# Peripherals.net
KiCad netlist of a schematic drawn in Altium Designer
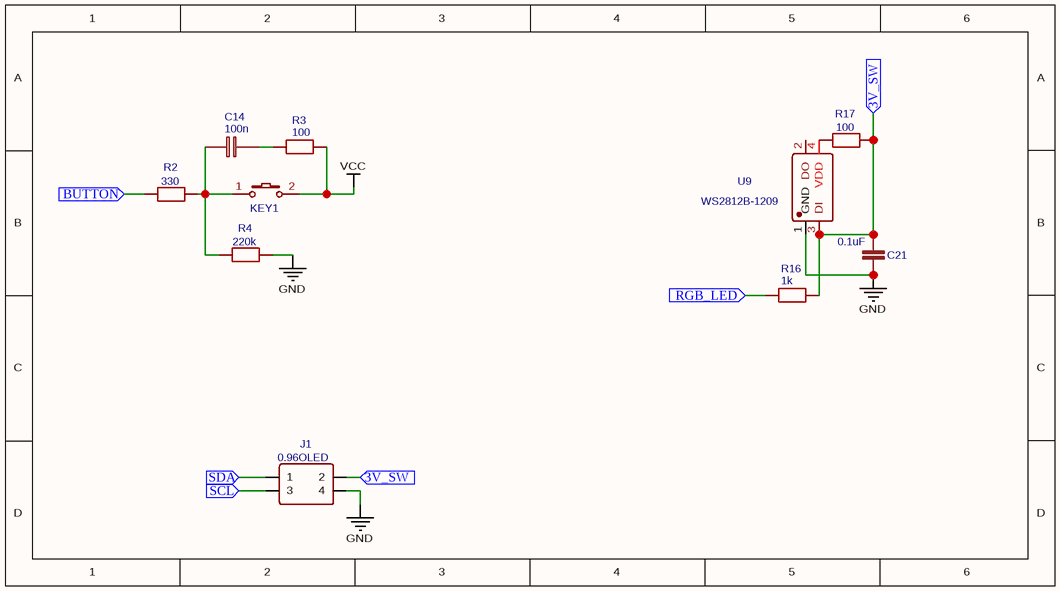
[diagram p0: Peripherals.schdoc]

(export (version "E")
  (design (tool "Eeschema 10.0.6"))
  (components
    (comp (ref "C14")
      (value "100n")
      (fields (field (name "CONTRIBUTOR") "LCEDA_Lib"))
      (libsource (lib "altium-import") (part "root_0_100n_"))
    )
    (comp (ref "C21")
      (value "0.1uF")
      (description "CAP-00810")
      (fields (field (name "CONTRIBUTOR") "SparkFun"))
      (libsource (lib "altium-import") (part "root_0_0.1uF_"))
    )
    (comp (ref "J1")
      (value "0.96OLED")
      (fields (field (name "BOM_SUPPLIER PART") "C66690") (field (name "CONTRIBUTOR") "LCEDA_Lib"))
      (libsource (lib "altium-import") (part "root_0_0.96OLED_"))
    )
    (comp (ref "KEY1")
      (value "K2-3.6×6.1_SMD")
      (fields
        (field (name "BOM_SUPPLIER PART") "C118141")
        (field (name "BOM_MANUFACTURER PART") "K2-1107ST-A4SW-06")
        (field (name "CONTRIBUTOR") "LCEDA_Lib")
      )
      (libsource (lib "altium-import") (part "root_0_K2-3.6×6.1_SMD_"))
    )
    (comp (ref "R2")
      (value "330")
      (fields (field (name "CONTRIBUTOR") "LCEDA_Lib"))
      (libsource (lib "altium-import") (part "root_0_330_"))
    )
    (comp (ref "R3")
      (value "100")
      (fields (field (name "CONTRIBUTOR") "LCEDA_Lib"))
      (libsource (lib "altium-import") (part "root_0_100_"))
    )
    (comp (ref "R4")
      (value "220k")
      (fields (field (name "CONTRIBUTOR") "LCEDA_Lib"))
      (libsource (lib "altium-import") (part "root_0_220k_"))
    )
    (comp (ref "R16")
      (value "1k")
      (fields
        (field (name "BOM_SUPPLIER PART") "C525388")
        (field (name "BOM_MANUFACTURER PART") "TCTR0603F47K0F3960T")
        (field (name "CONTRIBUTOR") "LCSC")
      )
      (libsource (lib "altium-import") (part "root_2_1k_"))
    )
    (comp (ref "R17")
      (value "100")
      (fields
        (field (name "BOM_SUPPLIER PART") "C525388")
        (field (name "BOM_MANUFACTURER PART") "TCTR0603F47K0F3960T")
        (field (name "CONTRIBUTOR") "LCSC")
      )
      (libsource (lib "altium-import") (part "root_0_100_"))
    )
    (comp (ref "U9")
      (value "WS2812B-1209")
      (fields (field (name "BOM_SUPPLIER PART") "C2835111") (field (name "CONTRIBUTOR") "LCSC"))
      (libsource (lib "altium-import") (part "root_1_WS2812B-1209_"))
    )
  )
  (nets
    (net (code "1") (name "/3V_SW") (class "Default")
      (node (ref "C21") (pin "1") (pinfunction "1_1") (pintype "passive"))
      (node (ref "J1") (pin "2") (pinfunction "2_2") (pintype "passive"))
      (node (ref "R16") (pin "1") (pinfunction "1_1") (pintype "passive"))
      (node (ref "R17") (pin "2") (pinfunction "2_2") (pintype "passive"))
      (node (ref "U9") (pin "3") (pinfunction "DI_3") (pintype "passive"))
    )
    (net (code "2") (name "/BUTTON") (class "Default")
      (node (ref "R2") (pin "1") (pinfunction "1_1") (pintype "passive"))
    )
    (net (code "3") (name "/RGB_LED") (class "Default")
      (node (ref "R16") (pin "2") (pinfunction "2_2") (pintype "passive"))
    )
    (net (code "4") (name "/SCL") (class "Default")
      (node (ref "J1") (pin "3") (pinfunction "3_3") (pintype "passive"))
    )
    (net (code "5") (name "/SDA") (class "Default")
      (node (ref "J1") (pin "1") (pinfunction "1_1") (pintype "passive"))
    )
    (net (code "6") (name "GND") (class "Default")
      (node (ref "C21") (pin "2") (pinfunction "2_2") (pintype "passive"))
      (node (ref "J1") (pin "4") (pinfunction "4_4") (pintype "passive"))
      (node (ref "R4") (pin "2") (pinfunction "2_2") (pintype "passive"))
      (node (ref "U9") (pin "1") (pinfunction "GND_1") (pintype "passive"))
    )
    (net (code "7") (name "Net-(C14-Pad1)") (class "Default")
      (node (ref "C14") (pin "1") (pinfunction "1_1") (pintype "passive"))
      (node (ref "KEY1") (pin "1") (pinfunction "1_1") (pintype "passive"))
      (node (ref "R2") (pin "2") (pinfunction "2_2") (pintype "passive"))
      (node (ref "R4") (pin "1") (pinfunction "1_1") (pintype "passive"))
    )
    (net (code "8") (name "Net-(C14-Pad2)") (class "Default")
      (node (ref "C14") (pin "2") (pinfunction "2_2") (pintype "passive"))
      (node (ref "R3") (pin "1") (pinfunction "1_1") (pintype "passive"))
    )
    (net (code "9") (name "Net-(U9-VDD)") (class "Default")
      (node (ref "R17") (pin "1") (pinfunction "1_1") (pintype "passive"))
      (node (ref "U9") (pin "4") (pinfunction "VDD_4") (pintype "passive"))
    )
    (net (code "10") (name "VCC") (class "Default")
      (node (ref "KEY1") (pin "2") (pinfunction "2_2") (pintype "passive"))
      (node (ref "R3") (pin "2") (pinfunction "2_2") (pintype "passive"))
    )
    (net (code "11") (name "unconnected-(U9-DO-Pad2)") (class "Default")
      (node (ref "U9") (pin "2") (pinfunction "DO_2") (pintype "passive"))
    )
  )
)
